# 13_RK3588_Flash_SD_Controller.net
KiCad netlist of a schematic drawn in Altium Designer
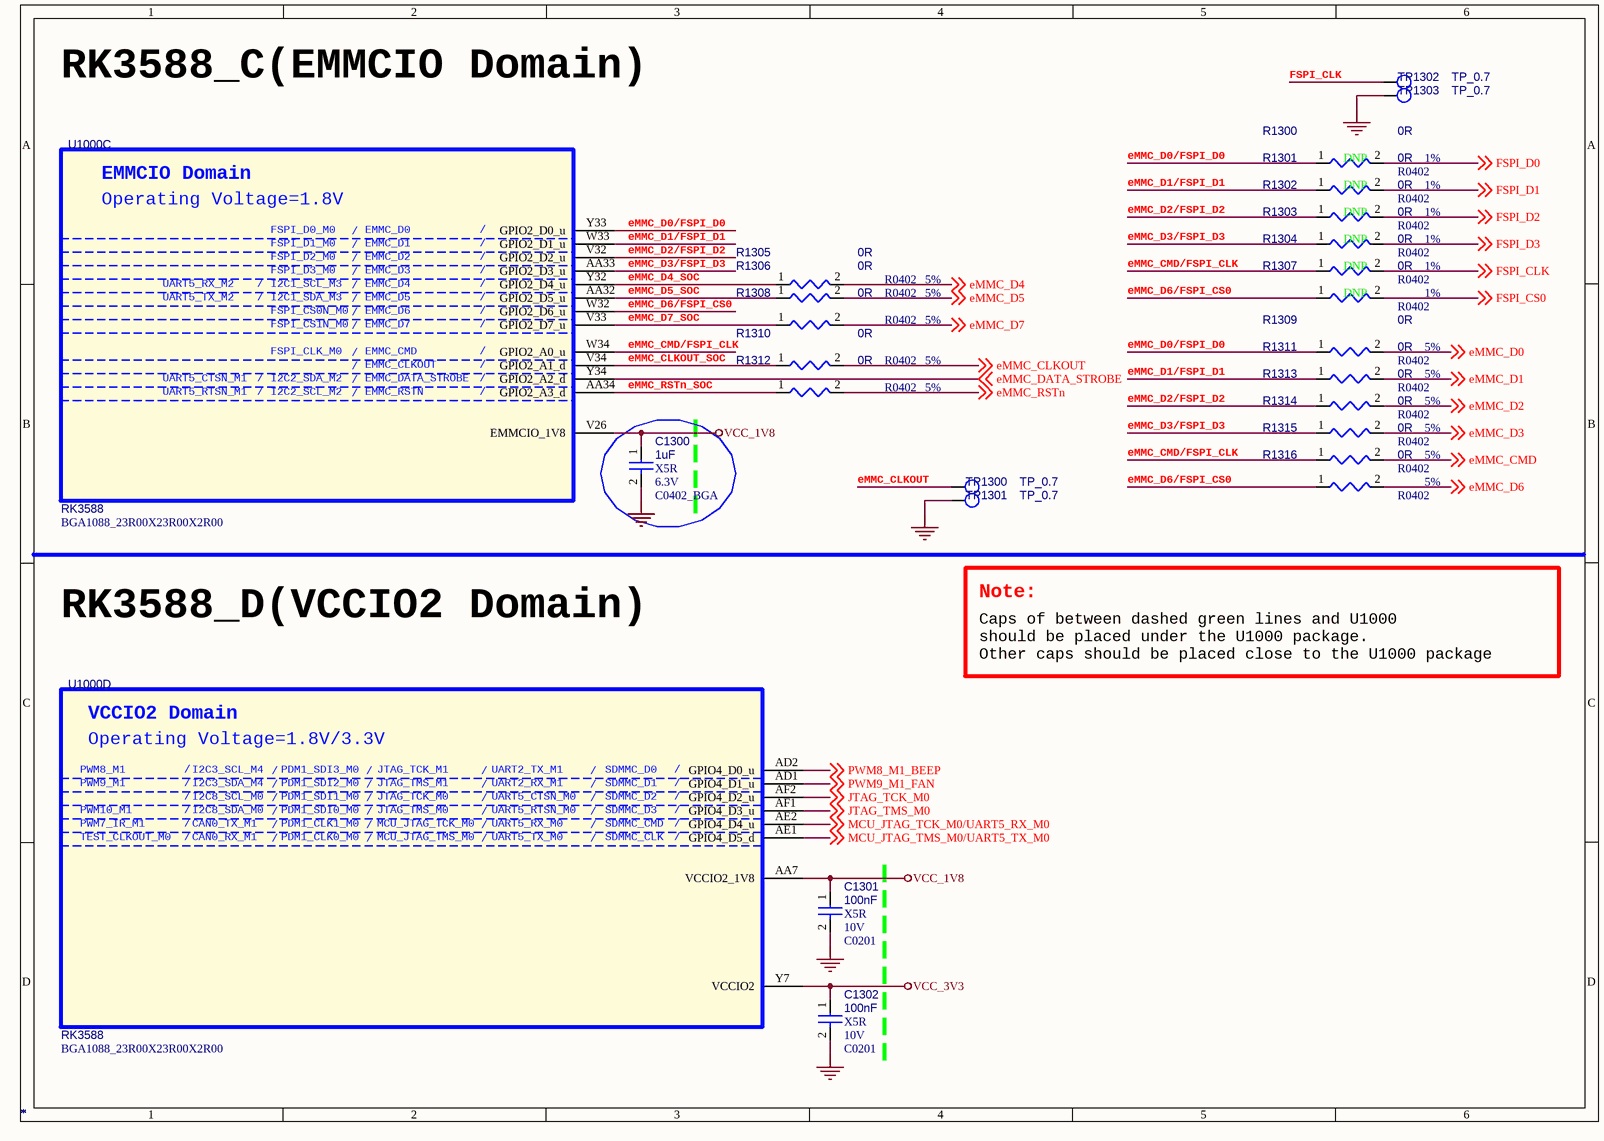
[diagram p0: 13.RK3588_Flash_SD Controller.SchDoc]

(export (version "E")
  (design (tool "Eeschema 10.0.6"))
  (components
    (comp (ref "C1300")
      (value "*")
      (footprint "C0402_BGA")
      (description "cap,1.00uF,+/-10%,6.3V,X5R,C0402")
      (fields
        (field (name "VOLTAGE") "6.3V")
        (field (name "PCB FOOTPRINT") "C0402_BGA")
        (field (name "DIELECTRIC") "X5R")
        (field (name "MANUFACTURER") "TDK")
        (field (name "TOLERANCE") "10%")
        (field (name "ALTIUM_UNNAMED_1") "1uF")
        (field (name "CREATED BY") "JJJ")
      )
      (libsource (lib "*") (part "CAP NP"))
    )
    (comp (ref "C1301")
      (value "*")
      (footprint "C0201")
      (description "cap,100.00nF,+/-10%,10V,X5R,C0201")
      (fields
        (field (name "VOLTAGE") "10V")
        (field (name "PCB FOOTPRINT") "C0201")
        (field (name "DIELECTRIC") "X5R")
        (field (name "MANUFACTURER") "TDK")
        (field (name "TOLERANCE") "10%")
        (field (name "ALTIUM_UNNAMED_1") "100nF")
        (field (name "CREATED BY") "JJJ")
      )
      (libsource (lib "*") (part "CAP NP"))
    )
    (comp (ref "C1302")
      (value "*")
      (footprint "C0201")
      (description "cap,100.00nF,+/-10%,10V,X5R,C0201")
      (fields
        (field (name "VOLTAGE") "10V")
        (field (name "PCB FOOTPRINT") "C0201")
        (field (name "DIELECTRIC") "X5R")
        (field (name "MANUFACTURER") "TDK")
        (field (name "TOLERANCE") "10%")
        (field (name "ALTIUM_UNNAMED_1") "100nF")
        (field (name "CREATED BY") "JJJ")
      )
      (libsource (lib "*") (part "CAP NP"))
    )
    (comp (ref "R1300")
      (value "*")
      (footprint "R0402")
      (description "НЁУГєсД¤µзЧи,0R,+/-1%,R0402,1/16W.")
      (fields
        (field (name "PCB FOOTPRINT") "R0402")
        (field (name "TOLERANCE") "1%")
        (field (name "MANUFACTURER") "YAGEO")
        (field (name "OPTION") "DNP")
        (field (name "ALTIUM_UNNAMED_1") "0R")
        (field (name "CREATED BY") "YTL")
      )
      (libsource (lib "*") (part "RESISTOR_Dup1"))
    )
    (comp (ref "R1301")
      (value "*")
      (footprint "R0402")
      (description "НЁУГєсД¤µзЧи,0R,+/-1%,R0402,1/16W.")
      (fields
        (field (name "PCB FOOTPRINT") "R0402")
        (field (name "TOLERANCE") "1%")
        (field (name "MANUFACTURER") "YAGEO")
        (field (name "OPTION") "DNP")
        (field (name "ALTIUM_UNNAMED_1") "0R")
        (field (name "CREATED BY") "YTL")
      )
      (libsource (lib "*") (part "RESISTOR_Dup1"))
    )
    (comp (ref "R1302")
      (value "*")
      (footprint "R0402")
      (description "НЁУГєсД¤µзЧи,0R,+/-1%,R0402,1/16W.")
      (fields
        (field (name "PCB FOOTPRINT") "R0402")
        (field (name "TOLERANCE") "1%")
        (field (name "MANUFACTURER") "YAGEO")
        (field (name "OPTION") "DNP")
        (field (name "ALTIUM_UNNAMED_1") "0R")
        (field (name "CREATED BY") "YTL")
      )
      (libsource (lib "*") (part "RESISTOR_Dup1"))
    )
    (comp (ref "R1303")
      (value "*")
      (footprint "R0402")
      (description "НЁУГєсД¤µзЧи,0R,+/-1%,R0402,1/16W.")
      (fields
        (field (name "PCB FOOTPRINT") "R0402")
        (field (name "TOLERANCE") "1%")
        (field (name "MANUFACTURER") "YAGEO")
        (field (name "OPTION") "DNP")
        (field (name "ALTIUM_UNNAMED_1") "0R")
        (field (name "CREATED BY") "YTL")
      )
      (libsource (lib "*") (part "RESISTOR_Dup1"))
    )
    (comp (ref "R1304")
      (value "*")
      (footprint "R0402")
      (description "НЁУГєсД¤µзЧи,0R,+/-1%,R0402,1/16W.")
      (fields
        (field (name "PCB FOOTPRINT") "R0402")
        (field (name "TOLERANCE") "1%")
        (field (name "MANUFACTURER") "YAGEO")
        (field (name "OPTION") "DNP")
        (field (name "ALTIUM_UNNAMED_1") "0R")
        (field (name "CREATED BY") "YTL")
      )
      (libsource (lib "*") (part "RESISTOR_Dup1"))
    )
    (comp (ref "R1305")
      (value "*")
      (footprint "R0402")
      (description "НЁУГєсД¤µзЧи,0R,+/-5%,R0402,1/16W.")
      (fields
        (field (name "PCB FOOTPRINT") "R0402")
        (field (name "TOLERANCE") "5%")
        (field (name "MANUFACTURER") "YAGEO")
        (field (name "ALTIUM_UNNAMED_1") "0R")
        (field (name "CREATED BY") "YTL")
      )
      (libsource (lib "*") (part "RESISTOR_Dup1"))
    )
    (comp (ref "R1306")
      (value "*")
      (footprint "R0402")
      (description "НЁУГєсД¤µзЧи,0R,+/-5%,R0402,1/16W.")
      (fields
        (field (name "PCB FOOTPRINT") "R0402")
        (field (name "TOLERANCE") "5%")
        (field (name "MANUFACTURER") "YAGEO")
        (field (name "ALTIUM_UNNAMED_1") "0R")
        (field (name "CREATED BY") "YTL")
      )
      (libsource (lib "*") (part "RESISTOR_Dup1"))
    )
    (comp (ref "R1307")
      (value "*")
      (footprint "R0402")
      (description "НЁУГєсД¤µзЧи,0R,+/-1%,R0402,1/16W.")
      (fields
        (field (name "PCB FOOTPRINT") "R0402")
        (field (name "TOLERANCE") "1%")
        (field (name "MANUFACTURER") "YAGEO")
        (field (name "OPTION") "DNP")
        (field (name "ALTIUM_UNNAMED_1") "0R")
        (field (name "CREATED BY") "YTL")
      )
      (libsource (lib "*") (part "RESISTOR_Dup1"))
    )
    (comp (ref "R1308")
      (value "*")
      (footprint "R0402")
      (description "НЁУГєсД¤µзЧи,0R,+/-5%,R0402,1/16W.")
      (fields
        (field (name "PCB FOOTPRINT") "R0402")
        (field (name "TOLERANCE") "5%")
        (field (name "MANUFACTURER") "YAGEO")
        (field (name "ALTIUM_UNNAMED_1") "0R")
        (field (name "CREATED BY") "YTL")
      )
      (libsource (lib "*") (part "RESISTOR_Dup1"))
    )
    (comp (ref "R1309")
      (value "*")
      (footprint "R0402")
      (description "НЁУГєсД¤µзЧи,0R,+/-5%,R0402,1/16W.")
      (fields
        (field (name "PCB FOOTPRINT") "R0402")
        (field (name "TOLERANCE") "5%")
        (field (name "MANUFACTURER") "YAGEO")
        (field (name "ALTIUM_UNNAMED_1") "0R")
        (field (name "CREATED BY") "YTL")
      )
      (libsource (lib "*") (part "RESISTOR_Dup1"))
    )
    (comp (ref "R1310")
      (value "*")
      (footprint "R0402")
      (description "НЁУГєсД¤µзЧи,0R,+/-5%,R0402,1/16W.")
      (fields
        (field (name "PCB FOOTPRINT") "R0402")
        (field (name "TOLERANCE") "5%")
        (field (name "MANUFACTURER") "YAGEO")
        (field (name "ALTIUM_UNNAMED_1") "0R")
        (field (name "CREATED BY") "YTL")
      )
      (libsource (lib "*") (part "RESISTOR_Dup1"))
    )
    (comp (ref "R1311")
      (value "*")
      (footprint "R0402")
      (description "НЁУГєсД¤µзЧи,0R,+/-5%,R0402,1/16W.")
      (fields
        (field (name "PCB FOOTPRINT") "R0402")
        (field (name "TOLERANCE") "5%")
        (field (name "MANUFACTURER") "YAGEO")
        (field (name "ALTIUM_UNNAMED_1") "0R")
        (field (name "CREATED BY") "YTL")
      )
      (libsource (lib "*") (part "RESISTOR_Dup1"))
    )
    (comp (ref "R1312")
      (value "*")
      (footprint "R0402")
      (description "НЁУГєсД¤µзЧи,0R,+/-5%,R0402,1/16W.")
      (fields
        (field (name "PCB FOOTPRINT") "R0402")
        (field (name "TOLERANCE") "5%")
        (field (name "MANUFACTURER") "YAGEO")
        (field (name "ALTIUM_UNNAMED_1") "0R")
        (field (name "CREATED BY") "YTL")
      )
      (libsource (lib "*") (part "RESISTOR_Dup1"))
    )
    (comp (ref "R1313")
      (value "*")
      (footprint "R0402")
      (description "НЁУГєсД¤µзЧи,0R,+/-5%,R0402,1/16W.")
      (fields
        (field (name "PCB FOOTPRINT") "R0402")
        (field (name "TOLERANCE") "5%")
        (field (name "MANUFACTURER") "YAGEO")
        (field (name "ALTIUM_UNNAMED_1") "0R")
        (field (name "CREATED BY") "YTL")
      )
      (libsource (lib "*") (part "RESISTOR_Dup1"))
    )
    (comp (ref "R1314")
      (value "*")
      (footprint "R0402")
      (description "НЁУГєсД¤µзЧи,0R,+/-5%,R0402,1/16W.")
      (fields
        (field (name "PCB FOOTPRINT") "R0402")
        (field (name "TOLERANCE") "5%")
        (field (name "MANUFACTURER") "YAGEO")
        (field (name "ALTIUM_UNNAMED_1") "0R")
        (field (name "CREATED BY") "YTL")
      )
      (libsource (lib "*") (part "RESISTOR_Dup1"))
    )
    (comp (ref "R1315")
      (value "*")
      (footprint "R0402")
      (description "НЁУГєсД¤µзЧи,0R,+/-5%,R0402,1/16W.")
      (fields
        (field (name "PCB FOOTPRINT") "R0402")
        (field (name "TOLERANCE") "5%")
        (field (name "MANUFACTURER") "YAGEO")
        (field (name "ALTIUM_UNNAMED_1") "0R")
        (field (name "CREATED BY") "YTL")
      )
      (libsource (lib "*") (part "RESISTOR_Dup1"))
    )
    (comp (ref "R1316")
      (value "*")
      (footprint "R0402")
      (description "НЁУГєсД¤µзЧи,0R,+/-5%,R0402,1/16W.")
      (fields
        (field (name "PCB FOOTPRINT") "R0402")
        (field (name "TOLERANCE") "5%")
        (field (name "MANUFACTURER") "YAGEO")
        (field (name "ALTIUM_UNNAMED_1") "0R")
        (field (name "CREATED BY") "YTL")
      )
      (libsource (lib "*") (part "RESISTOR_Dup1"))
    )
    (comp (ref "TP1300")
      (value "*")
      (footprint "TEST")
      (description "Test Point 0.7mm")
      (fields (field (name "ALTIUM_UNNAMED_1") "TP_0.7") (field (name "CREATED BY") "JJJ"))
      (libsource (lib "*") (part "TP"))
    )
    (comp (ref "TP1301")
      (value "*")
      (footprint "TEST")
      (description "Test Point 0.7mm")
      (fields (field (name "ALTIUM_UNNAMED_1") "TP_0.7") (field (name "CREATED BY") "JJJ"))
      (libsource (lib "*") (part "TP"))
    )
    (comp (ref "TP1302")
      (value "*")
      (footprint "TEST")
      (description "Test Point 0.7mm")
      (fields (field (name "ALTIUM_UNNAMED_1") "TP_0.7") (field (name "CREATED BY") "JJJ"))
      (libsource (lib "*") (part "TP"))
    )
    (comp (ref "TP1303")
      (value "*")
      (footprint "TEST")
      (description "Test Point 0.7mm")
      (fields (field (name "ALTIUM_UNNAMED_1") "TP_0.7") (field (name "CREATED BY") "JJJ"))
      (libsource (lib "*") (part "TP"))
    )
    (comp (ref "U1000")
      (value "*")
      (footprint "BGA1088_23R00X23R00X2R00")
      (description "ROCKCHIP SOC")
      (fields
        (field (name "MANUFACTURER") "Rockchip (ИрРѕОў)")
        (field (name "PCB FOOTPRINT") "BGA1088_23R00X23R00X2R00")
        (field (name "ALTIUM_UNNAMED_1") "RK3588")
        (field (name "CREATED BY") "YWQ")
      )
      (libsource (lib "*") (part "SOC_RK3588"))
    )
  )
  (nets
    (net (code "1") (name "/eMMC_CLKOUT_SOC") (class "Default")
      (node (ref "R1310") (pin "1") (pinfunction "1_1") (pintype "passive"))
      (node (ref "U1000") (pin "V34") (pinfunction "GPIO2_A1_d_V34") (pintype "passive"))
    )
    (net (code "2") (name "/eMMC_CMD{slash}FSPI_CLK") (class "Default")
      (node (ref "R1304") (pin "1") (pinfunction "1_1") (pintype "passive"))
      (node (ref "R1315") (pin "1") (pinfunction "1_1") (pintype "passive"))
      (node (ref "U1000") (pin "W34") (pinfunction "GPIO2_A0_u_W34") (pintype "passive"))
    )
    (net (code "3") (name "/eMMC_D0{slash}FSPI_D0") (class "Default")
      (node (ref "R1300") (pin "1") (pinfunction "1_1") (pintype "passive"))
      (node (ref "R1309") (pin "1") (pinfunction "1_1") (pintype "passive"))
      (node (ref "U1000") (pin "Y33") (pinfunction "GPIO2_D0_u_Y33") (pintype "passive"))
    )
    (net (code "4") (name "/eMMC_D1{slash}FSPI_D1") (class "Default")
      (node (ref "R1301") (pin "1") (pinfunction "1_1") (pintype "passive"))
      (node (ref "R1311") (pin "1") (pinfunction "1_1") (pintype "passive"))
      (node (ref "U1000") (pin "W33") (pinfunction "GPIO2_D1_u_W33") (pintype "passive"))
    )
    (net (code "5") (name "/eMMC_D2{slash}FSPI_D2") (class "Default")
      (node (ref "R1302") (pin "1") (pinfunction "1_1") (pintype "passive"))
      (node (ref "R1313") (pin "1") (pinfunction "1_1") (pintype "passive"))
      (node (ref "U1000") (pin "V32") (pinfunction "GPIO2_D2_u_V32") (pintype "passive"))
    )
    (net (code "6") (name "/eMMC_D3{slash}FSPI_D3") (class "Default")
      (node (ref "R1303") (pin "1") (pinfunction "1_1") (pintype "passive"))
      (node (ref "R1314") (pin "1") (pinfunction "1_1") (pintype "passive"))
      (node (ref "U1000") (pin "AA33") (pinfunction "GPIO2_D3_u_AA33") (pintype "passive"))
    )
    (net (code "7") (name "/eMMC_D4_SOC") (class "Default")
      (node (ref "R1305") (pin "1") (pinfunction "1_1") (pintype "passive"))
      (node (ref "U1000") (pin "Y32") (pinfunction "GPIO2_D4_u_Y32") (pintype "passive"))
    )
    (net (code "8") (name "/eMMC_D5_SOC") (class "Default")
      (node (ref "R1306") (pin "1") (pinfunction "1_1") (pintype "passive"))
      (node (ref "U1000") (pin "AA32") (pinfunction "GPIO2_D5_u_AA32") (pintype "passive"))
    )
    (net (code "9") (name "/eMMC_D6{slash}FSPI_CS0") (class "Default")
      (node (ref "R1307") (pin "1") (pinfunction "1_1") (pintype "passive"))
      (node (ref "R1316") (pin "1") (pinfunction "1_1") (pintype "passive"))
      (node (ref "U1000") (pin "W32") (pinfunction "GPIO2_D6_u_W32") (pintype "passive"))
    )
    (net (code "10") (name "/eMMC_D7_SOC") (class "Default")
      (node (ref "R1308") (pin "1") (pinfunction "1_1") (pintype "passive"))
      (node (ref "U1000") (pin "V33") (pinfunction "GPIO2_D7_u_V33") (pintype "passive"))
    )
    (net (code "11") (name "/eMMC_RSTn_SOC") (class "Default")
      (node (ref "R1312") (pin "1") (pinfunction "1_1") (pintype "passive"))
      (node (ref "U1000") (pin "AA34") (pinfunction "GPIO2_A3_d_AA34") (pintype "passive"))
    )
    (net (code "12") (name "FSPI_CLK") (class "Default")
      (node (ref "R1304") (pin "2") (pinfunction "2_2") (pintype "passive"))
      (node (ref "TP1302") (pin "1") (pinfunction "1_1") (pintype "passive"))
    )
    (net (code "13") (name "FSPI_CS0") (class "Default")
      (node (ref "R1307") (pin "2") (pinfunction "2_2") (pintype "passive"))
    )
    (net (code "14") (name "FSPI_D0") (class "Default")
      (node (ref "R1300") (pin "2") (pinfunction "2_2") (pintype "passive"))
    )
    (net (code "15") (name "FSPI_D1") (class "Default")
      (node (ref "R1301") (pin "2") (pinfunction "2_2") (pintype "passive"))
    )
    (net (code "16") (name "FSPI_D2") (class "Default")
      (node (ref "R1302") (pin "2") (pinfunction "2_2") (pintype "passive"))
    )
    (net (code "17") (name "FSPI_D3") (class "Default")
      (node (ref "R1303") (pin "2") (pinfunction "2_2") (pintype "passive"))
    )
    (net (code "18") (name "GND") (class "Default")
      (node (ref "C1300") (pin "2") (pinfunction "2_2") (pintype "passive"))
      (node (ref "C1301") (pin "2") (pinfunction "2_2") (pintype "passive"))
      (node (ref "C1302") (pin "2") (pinfunction "2_2") (pintype "passive"))
      (node (ref "TP1301") (pin "1") (pinfunction "1_1") (pintype "passive"))
      (node (ref "TP1303") (pin "1") (pinfunction "1_1") (pintype "passive"))
    )
    (net (code "19") (name "JTAG_TCK_M0") (class "Default")
      (node (ref "U1000") (pin "AF2") (pinfunction "GPIO4_D2_u_AF2") (pintype "passive"))
    )
    (net (code "20") (name "JTAG_TMS_M0") (class "Default")
      (node (ref "U1000") (pin "AF1") (pinfunction "GPIO4_D3_u_AF1") (pintype "passive"))
    )
    (net (code "21") (name "MCU_JTAG_TCK_M0{slash}UART5_RX_M0") (class "Default")
      (node (ref "U1000") (pin "AE2") (pinfunction "GPIO4_D4_u_AE2") (pintype "passive"))
    )
    (net (code "22") (name "MCU_JTAG_TMS_M0{slash}UART5_TX_M0") (class "Default")
      (node (ref "U1000") (pin "AE1") (pinfunction "GPIO4_D5_d_AE1") (pintype "passive"))
    )
    (net (code "23") (name "PWM8_M1_BEEP") (class "Default")
      (node (ref "U1000") (pin "AD2") (pinfunction "GPIO4_D0_u_AD2") (pintype "passive"))
    )
    (net (code "24") (name "PWM9_M1_FAN") (class "Default")
      (node (ref "U1000") (pin "AD1") (pinfunction "GPIO4_D1_u_AD1") (pintype "passive"))
    )
    (net (code "25") (name "VCC_1V8") (class "Default")
      (node (ref "C1300") (pin "1") (pinfunction "1_1") (pintype "passive"))
      (node (ref "C1301") (pin "1") (pinfunction "1_1") (pintype "passive"))
      (node (ref "U1000") (pin "AA7") (pinfunction "VCCIO2_1V8_AA7") (pintype "power_in"))
      (node (ref "U1000") (pin "V26") (pinfunction "EMMCIO_1V8_V26") (pintype "power_in"))
    )
    (net (code "26") (name "VCC_3V3") (class "Default")
      (node (ref "C1302") (pin "1") (pinfunction "1_1") (pintype "passive"))
      (node (ref "U1000") (pin "Y7") (pinfunction "VCCIO2_Y7") (pintype "power_in"))
    )
    (net (code "27") (name "eMMC_CLKOUT") (class "Default")
      (node (ref "R1310") (pin "2") (pinfunction "2_2") (pintype "passive"))
      (node (ref "TP1300") (pin "1") (pinfunction "1_1") (pintype "passive"))
    )
    (net (code "28") (name "eMMC_CMD") (class "Default")
      (node (ref "R1315") (pin "2") (pinfunction "2_2") (pintype "passive"))
    )
    (net (code "29") (name "eMMC_D0") (class "Default")
      (node (ref "R1309") (pin "2") (pinfunction "2_2") (pintype "passive"))
    )
    (net (code "30") (name "eMMC_D1") (class "Default")
      (node (ref "R1311") (pin "2") (pinfunction "2_2") (pintype "passive"))
    )
    (net (code "31") (name "eMMC_D2") (class "Default")
      (node (ref "R1313") (pin "2") (pinfunction "2_2") (pintype "passive"))
    )
    (net (code "32") (name "eMMC_D3") (class "Default")
      (node (ref "R1314") (pin "2") (pinfunction "2_2") (pintype "passive"))
    )
    (net (code "33") (name "eMMC_D4") (class "Default")
      (node (ref "R1305") (pin "2") (pinfunction "2_2") (pintype "passive"))
    )
    (net (code "34") (name "eMMC_D5") (class "Default")
      (node (ref "R1306") (pin "2") (pinfunction "2_2") (pintype "passive"))
    )
    (net (code "35") (name "eMMC_D6") (class "Default")
      (node (ref "R1316") (pin "2") (pinfunction "2_2") (pintype "passive"))
    )
    (net (code "36") (name "eMMC_D7") (class "Default")
      (node (ref "R1308") (pin "2") (pinfunction "2_2") (pintype "passive"))
    )
    (net (code "37") (name "eMMC_DATA_STROBE") (class "Default")
      (node (ref "U1000") (pin "Y34") (pinfunction "GPIO2_A2_d_Y34") (pintype "passive"))
    )
    (net (code "38") (name "eMMC_RSTn") (class "Default")
      (node (ref "R1312") (pin "2") (pinfunction "2_2") (pintype "passive"))
    )
  )
)
